# sch_substrate_board_zynq.net
KiCad netlist of a schematic drawn in Altium Designer
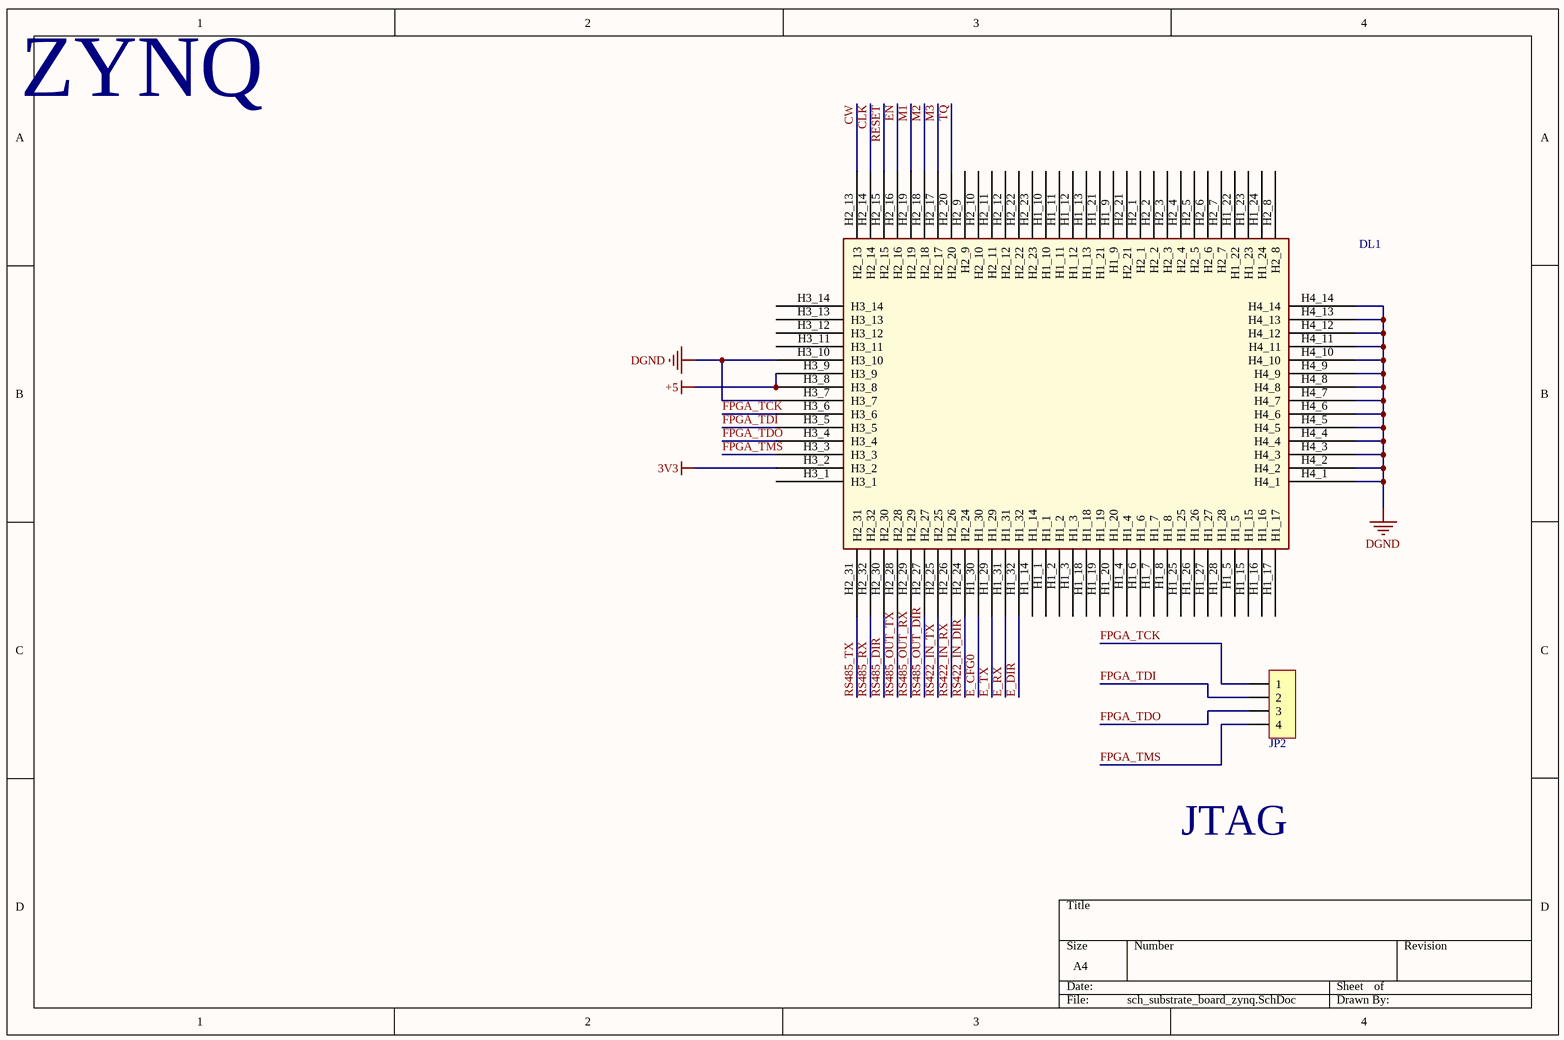
[diagram p0: sch_substrate_board_zynq.SchDoc]

(export (version "E")
  (design (tool "Eeschema 10.0.6"))
  (components
    (comp (ref "DL1") (value "SSH") (footprint "SSH") (libsource (lib "prj_sig_dl1") (part "SSH")))
    (comp (ref "JP2")
      (value "HDR-1X4")
      (footprint "XH2.54-LI-4P")
      (description "4P接插件")
      (fields (field (name "版权归属") "封装库来自淘宝 ID：黄晶宝石"))
      (libsource (lib "5.4 - 接插件-脚距2.54 (100mil) ") (part "Header 4"))
    )
  )
  (nets
    (net (code "1") (name "+5") (class "Default")
      (node (ref "DL1") (pin "H3_8") (pinfunction "H3_8_H3_8") (pintype "passive"))
      (node (ref "DL1") (pin "H3_9") (pinfunction "H3_9_H3_9") (pintype "passive"))
    )
    (net (code "2") (name "/CLK") (class "Default")
      (node (ref "DL1") (pin "H2_14") (pinfunction "H2_14_H2_14") (pintype "passive"))
    )
    (net (code "3") (name "/CW") (class "Default")
      (node (ref "DL1") (pin "H2_13") (pinfunction "H2_13_H2_13") (pintype "passive"))
    )
    (net (code "4") (name "/EN") (class "Default")
      (node (ref "DL1") (pin "H2_16") (pinfunction "H2_16_H2_16") (pintype "passive"))
    )
    (net (code "5") (name "/E_CFG0") (class "Default")
      (node (ref "DL1") (pin "H1_30") (pinfunction "H1_30_H1_30") (pintype "passive"))
    )
    (net (code "6") (name "/E_DIR") (class "Default")
      (node (ref "DL1") (pin "H1_32") (pinfunction "H1_32_H1_32") (pintype "passive"))
    )
    (net (code "7") (name "/E_RX") (class "Default")
      (node (ref "DL1") (pin "H1_31") (pinfunction "H1_31_H1_31") (pintype "passive"))
    )
    (net (code "8") (name "/E_TX") (class "Default")
      (node (ref "DL1") (pin "H1_29") (pinfunction "H1_29_H1_29") (pintype "passive"))
    )
    (net (code "9") (name "/FPGA_TCK") (class "Default")
      (node (ref "DL1") (pin "H3_6") (pinfunction "H3_6_H3_6") (pintype "passive"))
      (node (ref "JP2") (pin "1") (pinfunction "1_1") (pintype "passive"))
    )
    (net (code "10") (name "/FPGA_TDI") (class "Default")
      (node (ref "DL1") (pin "H3_5") (pinfunction "H3_5_H3_5") (pintype "passive"))
      (node (ref "JP2") (pin "2") (pinfunction "2_2") (pintype "passive"))
    )
    (net (code "11") (name "/FPGA_TDO") (class "Default")
      (node (ref "DL1") (pin "H3_4") (pinfunction "H3_4_H3_4") (pintype "passive"))
      (node (ref "JP2") (pin "3") (pinfunction "3_3") (pintype "passive"))
    )
    (net (code "12") (name "/FPGA_TMS") (class "Default")
      (node (ref "DL1") (pin "H3_3") (pinfunction "H3_3_H3_3") (pintype "passive"))
      (node (ref "JP2") (pin "4") (pinfunction "4_4") (pintype "passive"))
    )
    (net (code "13") (name "/M1") (class "Default")
      (node (ref "DL1") (pin "H2_19") (pinfunction "H2_19_H2_19") (pintype "passive"))
    )
    (net (code "14") (name "/M2") (class "Default")
      (node (ref "DL1") (pin "H2_18") (pinfunction "H2_18_H2_18") (pintype "passive"))
    )
    (net (code "15") (name "/M3") (class "Default")
      (node (ref "DL1") (pin "H2_17") (pinfunction "H2_17_H2_17") (pintype "passive"))
    )
    (net (code "16") (name "/RESET") (class "Default")
      (node (ref "DL1") (pin "H2_15") (pinfunction "H2_15_H2_15") (pintype "passive"))
    )
    (net (code "17") (name "/RS422_IN_DIR") (class "Default")
      (node (ref "DL1") (pin "H2_24") (pinfunction "H2_24_H2_24") (pintype "passive"))
    )
    (net (code "18") (name "/RS422_IN_RX") (class "Default")
      (node (ref "DL1") (pin "H2_26") (pinfunction "H2_26_H2_26") (pintype "passive"))
    )
    (net (code "19") (name "/RS422_IN_TX") (class "Default")
      (node (ref "DL1") (pin "H2_25") (pinfunction "H2_25_H2_25") (pintype "passive"))
    )
    (net (code "20") (name "/RS485_DIR") (class "Default")
      (node (ref "DL1") (pin "H2_30") (pinfunction "H2_30_H2_30") (pintype "passive"))
    )
    (net (code "21") (name "/RS485_OUT_DIR") (class "Default")
      (node (ref "DL1") (pin "H2_27") (pinfunction "H2_27_H2_27") (pintype "passive"))
    )
    (net (code "22") (name "/RS485_OUT_RX") (class "Default")
      (node (ref "DL1") (pin "H2_29") (pinfunction "H2_29_H2_29") (pintype "passive"))
    )
    (net (code "23") (name "/RS485_OUT_TX") (class "Default")
      (node (ref "DL1") (pin "H2_28") (pinfunction "H2_28_H2_28") (pintype "passive"))
    )
    (net (code "24") (name "/RS485_RX") (class "Default")
      (node (ref "DL1") (pin "H2_32") (pinfunction "H2_32_H2_32") (pintype "passive"))
    )
    (net (code "25") (name "/RS485_TX") (class "Default")
      (node (ref "DL1") (pin "H2_31") (pinfunction "H2_31_H2_31") (pintype "passive"))
    )
    (net (code "26") (name "/TQ") (class "Default")
      (node (ref "DL1") (pin "H2_20") (pinfunction "H2_20_H2_20") (pintype "passive"))
    )
    (net (code "27") (name "3V3") (class "Default")
      (node (ref "DL1") (pin "H3_2") (pinfunction "H3_2_H3_2") (pintype "passive"))
    )
    (net (code "28") (name "DGND") (class "Default")
      (node (ref "DL1") (pin "H3_10") (pinfunction "H3_10_H3_10") (pintype "passive"))
      (node (ref "DL1") (pin "H3_7") (pinfunction "H3_7_H3_7") (pintype "passive"))
      (node (ref "DL1") (pin "H4_1") (pinfunction "H4_1_H4_1") (pintype "passive"))
      (node (ref "DL1") (pin "H4_10") (pinfunction "H4_10_H4_10") (pintype "passive"))
      (node (ref "DL1") (pin "H4_11") (pinfunction "H4_11_H4_11") (pintype "passive"))
      (node (ref "DL1") (pin "H4_12") (pinfunction "H4_12_H4_12") (pintype "passive"))
      (node (ref "DL1") (pin "H4_13") (pinfunction "H4_13_H4_13") (pintype "passive"))
      (node (ref "DL1") (pin "H4_14") (pinfunction "H4_14_H4_14") (pintype "passive"))
      (node (ref "DL1") (pin "H4_2") (pinfunction "H4_2_H4_2") (pintype "passive"))
      (node (ref "DL1") (pin "H4_3") (pinfunction "H4_3_H4_3") (pintype "passive"))
      (node (ref "DL1") (pin "H4_4") (pinfunction "H4_4_H4_4") (pintype "passive"))
      (node (ref "DL1") (pin "H4_5") (pinfunction "H4_5_H4_5") (pintype "passive"))
      (node (ref "DL1") (pin "H4_6") (pinfunction "H4_6_H4_6") (pintype "passive"))
      (node (ref "DL1") (pin "H4_7") (pinfunction "H4_7_H4_7") (pintype "passive"))
      (node (ref "DL1") (pin "H4_8") (pinfunction "H4_8_H4_8") (pintype "passive"))
      (node (ref "DL1") (pin "H4_9") (pinfunction "H4_9_H4_9") (pintype "passive"))
    )
    (net (code "29") (name "unconnected-(DL1-PadH1_1)") (class "Default")
      (node (ref "DL1") (pin "H1_1") (pinfunction "H1_1_H1_1") (pintype "passive"))
    )
    (net (code "30") (name "unconnected-(DL1-PadH1_2)") (class "Default")
      (node (ref "DL1") (pin "H1_2") (pinfunction "H1_2_H1_2") (pintype "passive"))
    )
    (net (code "31") (name "unconnected-(DL1-PadH1_3)") (class "Default")
      (node (ref "DL1") (pin "H1_3") (pinfunction "H1_3_H1_3") (pintype "passive"))
    )
    (net (code "32") (name "unconnected-(DL1-PadH1_4)") (class "Default")
      (node (ref "DL1") (pin "H1_4") (pinfunction "H1_4_H1_4") (pintype "passive"))
    )
    (net (code "33") (name "unconnected-(DL1-PadH1_5)") (class "Default")
      (node (ref "DL1") (pin "H1_5") (pinfunction "H1_5_H1_5") (pintype "passive"))
    )
    (net (code "34") (name "unconnected-(DL1-PadH1_6)") (class "Default")
      (node (ref "DL1") (pin "H1_6") (pinfunction "H1_6_H1_6") (pintype "passive"))
    )
    (net (code "35") (name "unconnected-(DL1-PadH1_7)") (class "Default")
      (node (ref "DL1") (pin "H1_7") (pinfunction "H1_7_H1_7") (pintype "passive"))
    )
    (net (code "36") (name "unconnected-(DL1-PadH1_8)") (class "Default")
      (node (ref "DL1") (pin "H1_8") (pinfunction "H1_8_H1_8") (pintype "passive"))
    )
    (net (code "37") (name "unconnected-(DL1-PadH1_9)") (class "Default")
      (node (ref "DL1") (pin "H1_9") (pinfunction "H1_9_H1_9") (pintype "passive"))
    )
    (net (code "38") (name "unconnected-(DL1-PadH1_10)") (class "Default")
      (node (ref "DL1") (pin "H1_10") (pinfunction "H1_10_H1_10") (pintype "passive"))
    )
    (net (code "39") (name "unconnected-(DL1-PadH1_11)") (class "Default")
      (node (ref "DL1") (pin "H1_11") (pinfunction "H1_11_H1_11") (pintype "passive"))
    )
    (net (code "40") (name "unconnected-(DL1-PadH1_12)") (class "Default")
      (node (ref "DL1") (pin "H1_12") (pinfunction "H1_12_H1_12") (pintype "passive"))
    )
    (net (code "41") (name "unconnected-(DL1-PadH1_13)") (class "Default")
      (node (ref "DL1") (pin "H1_13") (pinfunction "H1_13_H1_13") (pintype "passive"))
    )
    (net (code "42") (name "unconnected-(DL1-PadH1_14)") (class "Default")
      (node (ref "DL1") (pin "H1_14") (pinfunction "H1_14_H1_14") (pintype "passive"))
    )
    (net (code "43") (name "unconnected-(DL1-PadH1_15)") (class "Default")
      (node (ref "DL1") (pin "H1_15") (pinfunction "H1_15_H1_15") (pintype "passive"))
    )
    (net (code "44") (name "unconnected-(DL1-PadH1_16)") (class "Default")
      (node (ref "DL1") (pin "H1_16") (pinfunction "H1_16_H1_16") (pintype "passive"))
    )
    (net (code "45") (name "unconnected-(DL1-PadH1_17)") (class "Default")
      (node (ref "DL1") (pin "H1_17") (pinfunction "H1_17_H1_17") (pintype "passive"))
    )
    (net (code "46") (name "unconnected-(DL1-PadH1_18)") (class "Default")
      (node (ref "DL1") (pin "H1_18") (pinfunction "H1_18_H1_18") (pintype "passive"))
    )
    (net (code "47") (name "unconnected-(DL1-PadH1_19)") (class "Default")
      (node (ref "DL1") (pin "H1_19") (pinfunction "H1_19_H1_19") (pintype "passive"))
    )
    (net (code "48") (name "unconnected-(DL1-PadH1_20)") (class "Default")
      (node (ref "DL1") (pin "H1_20") (pinfunction "H1_20_H1_20") (pintype "passive"))
    )
    (net (code "49") (name "unconnected-(DL1-PadH1_21)") (class "Default")
      (node (ref "DL1") (pin "H1_21") (pinfunction "H1_21_H1_21") (pintype "passive"))
    )
    (net (code "50") (name "unconnected-(DL1-PadH1_22)") (class "Default")
      (node (ref "DL1") (pin "H1_22") (pinfunction "H1_22_H1_22") (pintype "passive"))
    )
    (net (code "51") (name "unconnected-(DL1-PadH1_23)") (class "Default")
      (node (ref "DL1") (pin "H1_23") (pinfunction "H1_23_H1_23") (pintype "passive"))
    )
    (net (code "52") (name "unconnected-(DL1-PadH1_24)") (class "Default")
      (node (ref "DL1") (pin "H1_24") (pinfunction "H1_24_H1_24") (pintype "passive"))
    )
    (net (code "53") (name "unconnected-(DL1-PadH1_25)") (class "Default")
      (node (ref "DL1") (pin "H1_25") (pinfunction "H1_25_H1_25") (pintype "passive"))
    )
    (net (code "54") (name "unconnected-(DL1-PadH1_26)") (class "Default")
      (node (ref "DL1") (pin "H1_26") (pinfunction "H1_26_H1_26") (pintype "passive"))
    )
    (net (code "55") (name "unconnected-(DL1-PadH1_27)") (class "Default")
      (node (ref "DL1") (pin "H1_27") (pinfunction "H1_27_H1_27") (pintype "passive"))
    )
    (net (code "56") (name "unconnected-(DL1-PadH1_28)") (class "Default")
      (node (ref "DL1") (pin "H1_28") (pinfunction "H1_28_H1_28") (pintype "passive"))
    )
    (net (code "57") (name "unconnected-(DL1-PadH2_1)") (class "Default")
      (node (ref "DL1") (pin "H2_1") (pinfunction "H2_1_H2_1") (pintype "passive"))
    )
    (net (code "58") (name "unconnected-(DL1-PadH2_2)") (class "Default")
      (node (ref "DL1") (pin "H2_2") (pinfunction "H2_2_H2_2") (pintype "passive"))
    )
    (net (code "59") (name "unconnected-(DL1-PadH2_3)") (class "Default")
      (node (ref "DL1") (pin "H2_3") (pinfunction "H2_3_H2_3") (pintype "passive"))
    )
    (net (code "60") (name "unconnected-(DL1-PadH2_4)") (class "Default")
      (node (ref "DL1") (pin "H2_4") (pinfunction "H2_4_H2_4") (pintype "passive"))
    )
    (net (code "61") (name "unconnected-(DL1-PadH2_5)") (class "Default")
      (node (ref "DL1") (pin "H2_5") (pinfunction "H2_5_H2_5") (pintype "passive"))
    )
    (net (code "62") (name "unconnected-(DL1-PadH2_6)") (class "Default")
      (node (ref "DL1") (pin "H2_6") (pinfunction "H2_6_H2_6") (pintype "passive"))
    )
    (net (code "63") (name "unconnected-(DL1-PadH2_7)") (class "Default")
      (node (ref "DL1") (pin "H2_7") (pinfunction "H2_7_H2_7") (pintype "passive"))
    )
    (net (code "64") (name "unconnected-(DL1-PadH2_8)") (class "Default")
      (node (ref "DL1") (pin "H2_8") (pinfunction "H2_8_H2_8") (pintype "passive"))
    )
    (net (code "65") (name "unconnected-(DL1-PadH2_9)") (class "Default")
      (node (ref "DL1") (pin "H2_9") (pinfunction "H2_9_H2_9") (pintype "passive"))
    )
    (net (code "66") (name "unconnected-(DL1-PadH2_10)") (class "Default")
      (node (ref "DL1") (pin "H2_10") (pinfunction "H2_10_H2_10") (pintype "passive"))
    )
    (net (code "67") (name "unconnected-(DL1-PadH2_11)") (class "Default")
      (node (ref "DL1") (pin "H2_11") (pinfunction "H2_11_H2_11") (pintype "passive"))
    )
    (net (code "68") (name "unconnected-(DL1-PadH2_12)") (class "Default")
      (node (ref "DL1") (pin "H2_12") (pinfunction "H2_12_H2_12") (pintype "passive"))
    )
    (net (code "69") (name "unconnected-(DL1-PadH2_21)") (class "Default")
      (node (ref "DL1") (pin "H2_21") (pinfunction "H2_21_H2_21") (pintype "passive"))
    )
    (net (code "70") (name "unconnected-(DL1-PadH2_22)") (class "Default")
      (node (ref "DL1") (pin "H2_22") (pinfunction "H2_22_H2_22") (pintype "passive"))
    )
    (net (code "71") (name "unconnected-(DL1-PadH2_23)") (class "Default")
      (node (ref "DL1") (pin "H2_23") (pinfunction "H2_23_H2_23") (pintype "passive"))
    )
    (net (code "72") (name "unconnected-(DL1-PadH3_1)") (class "Default")
      (node (ref "DL1") (pin "H3_1") (pinfunction "H3_1_H3_1") (pintype "passive"))
    )
    (net (code "73") (name "unconnected-(DL1-PadH3_11)") (class "Default")
      (node (ref "DL1") (pin "H3_11") (pinfunction "H3_11_H3_11") (pintype "passive"))
    )
    (net (code "74") (name "unconnected-(DL1-PadH3_12)") (class "Default")
      (node (ref "DL1") (pin "H3_12") (pinfunction "H3_12_H3_12") (pintype "passive"))
    )
    (net (code "75") (name "unconnected-(DL1-PadH3_13)") (class "Default")
      (node (ref "DL1") (pin "H3_13") (pinfunction "H3_13_H3_13") (pintype "passive"))
    )
    (net (code "76") (name "unconnected-(DL1-PadH3_14)") (class "Default")
      (node (ref "DL1") (pin "H3_14") (pinfunction "H3_14_H3_14") (pintype "passive"))
    )
  )
)
